# Pair_3.net
KiCad netlist of a schematic drawn in Altium Designer
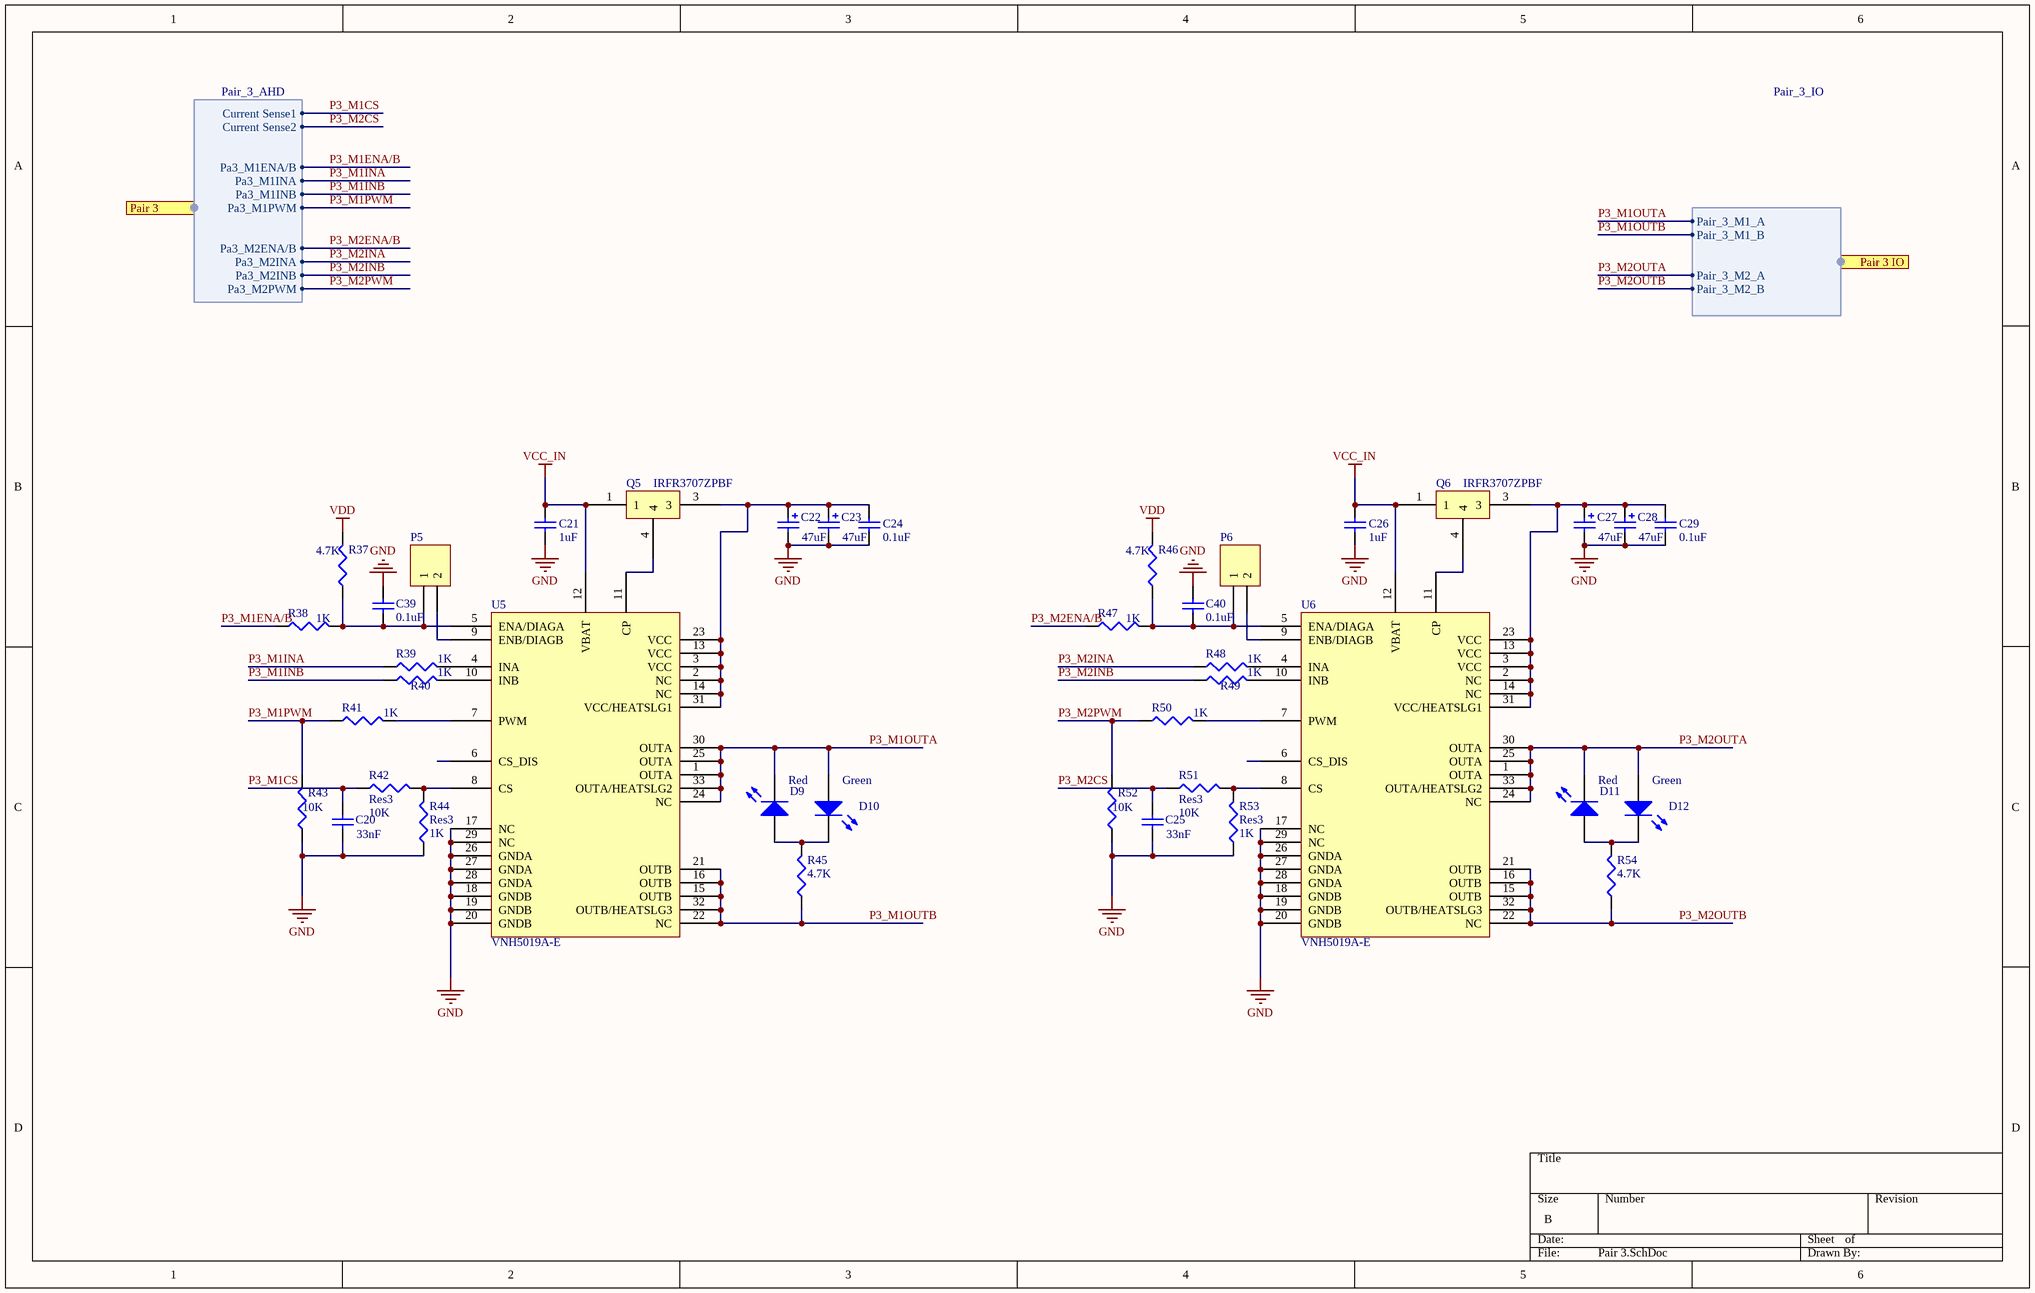
[diagram p0: Pair 3.SchDoc]

(export (version "E")
  (design (tool "Eeschema 10.0.6"))
  (components
    (comp (ref "C20")
      (value "33nF")
      (footprint "1608[0603]")
      (description "Capacitor (Semiconductor SIM Model)")
      (fields (field (name "Comment") "Cap Semi") (field (name "PUBLISHER") "Altium Limited"))
      (libsource (lib "Miscellaneous Devices") (part "Cap Semi"))
    )
    (comp (ref "C21")
      (value "1uF")
      (footprint "1608[0603]")
      (description "Capacitor (Semiconductor SIM Model)")
      (fields (field (name "Comment") "Cap Semi") (field (name "PUBLISHER") "Altium Limited"))
      (libsource (lib "Miscellaneous Devices") (part "Cap Semi"))
    )
    (comp (ref "C22")
      (value "47uF")
      (footprint "CAPPR2-5x6.8")
      (description "Polarized Capacitor (Axial)")
      (fields (field (name "Comment") "Cap Pol2") (field (name "PUBLISHER") "Altium Limited"))
      (libsource (lib "Miscellaneous Devices") (part "Cap Pol2"))
    )
    (comp (ref "C23")
      (value "47uF")
      (footprint "CAPPR2-5x6.8")
      (description "Polarized Capacitor (Axial)")
      (fields (field (name "Comment") "Cap Pol2") (field (name "PUBLISHER") "Altium Limited"))
      (libsource (lib "Miscellaneous Devices") (part "Cap Pol2"))
    )
    (comp (ref "C24")
      (value "0.1uF")
      (footprint "C1206")
      (description "Capacitor (Semiconductor SIM Model)")
      (fields (field (name "Comment") "Cap Semi") (field (name "PUBLISHER") "Altium Limited"))
      (libsource (lib "Miscellaneous Devices") (part "Cap Semi"))
    )
    (comp (ref "C25")
      (value "33nF")
      (footprint "1608[0603]")
      (description "Capacitor (Semiconductor SIM Model)")
      (fields (field (name "Comment") "Cap Semi") (field (name "PUBLISHER") "Altium Limited"))
      (libsource (lib "Miscellaneous Devices") (part "Cap Semi"))
    )
    (comp (ref "C26")
      (value "1uF")
      (footprint "1608[0603]")
      (description "Capacitor (Semiconductor SIM Model)")
      (fields (field (name "Comment") "Cap Semi") (field (name "PUBLISHER") "Altium Limited"))
      (libsource (lib "Miscellaneous Devices") (part "Cap Semi"))
    )
    (comp (ref "C27")
      (value "47uF")
      (footprint "CAPPR2-5x6.8")
      (description "Polarized Capacitor (Axial)")
      (fields (field (name "Comment") "Cap Pol2") (field (name "PUBLISHER") "Altium Limited"))
      (libsource (lib "Miscellaneous Devices") (part "Cap Pol2"))
    )
    (comp (ref "C28")
      (value "47uF")
      (footprint "CAPPR2-5x6.8")
      (description "Polarized Capacitor (Axial)")
      (fields (field (name "Comment") "Cap Pol2") (field (name "PUBLISHER") "Altium Limited"))
      (libsource (lib "Miscellaneous Devices") (part "Cap Pol2"))
    )
    (comp (ref "C29")
      (value "0.1uF")
      (footprint "C1206")
      (description "Capacitor (Semiconductor SIM Model)")
      (fields (field (name "Comment") "Cap Semi") (field (name "PUBLISHER") "Altium Limited"))
      (libsource (lib "Miscellaneous Devices") (part "Cap Semi"))
    )
    (comp (ref "C39")
      (value "0.1uF")
      (footprint "1608[0603]")
      (description "Capacitor (Semiconductor SIM Model)")
      (fields (field (name "Comment") "Cap Semi") (field (name "PUBLISHER") "Altium Limited"))
      (libsource (lib "Miscellaneous Devices") (part "Cap Semi"))
    )
    (comp (ref "C40")
      (value "0.1uF")
      (footprint "1608[0603]")
      (description "Capacitor (Semiconductor SIM Model)")
      (fields (field (name "Comment") "Cap Semi") (field (name "PUBLISHER") "Altium Limited"))
      (libsource (lib "Miscellaneous Devices") (part "Cap Semi"))
    )
    (comp (ref "D9")
      (value "LED2")
      (footprint "3.2X1.6X1.1")
      (description "Typical RED, GREEN, YELLOW, AMBER GaAs LED")
      (fields (field (name "PUBLISHER") "Altium Limited"))
      (libsource (lib "Miscellaneous Devices") (part "LED2"))
    )
    (comp (ref "D10")
      (value "LED2")
      (footprint "3.2X1.6X1.1")
      (description "Typical RED, GREEN, YELLOW, AMBER GaAs LED")
      (fields (field (name "PUBLISHER") "Altium Limited"))
      (libsource (lib "Miscellaneous Devices") (part "LED2"))
    )
    (comp (ref "D11")
      (value "LED2")
      (footprint "3.2X1.6X1.1")
      (description "Typical RED, GREEN, YELLOW, AMBER GaAs LED")
      (fields (field (name "PUBLISHER") "Altium Limited"))
      (libsource (lib "Miscellaneous Devices") (part "LED2"))
    )
    (comp (ref "D12")
      (value "LED2")
      (footprint "3.2X1.6X1.1")
      (description "Typical RED, GREEN, YELLOW, AMBER GaAs LED")
      (fields (field (name "PUBLISHER") "Altium Limited"))
      (libsource (lib "Miscellaneous Devices") (part "LED2"))
    )
    (comp (ref "P5")
      (value "Header 2")
      (footprint "HDR1X2")
      (description "Header, 2-Pin")
      (fields (field (name "PUBLISHER") "Altium Limited"))
      (libsource (lib "Miscellaneous Connectors") (part "Header 2"))
    )
    (comp (ref "P6")
      (value "Header 2")
      (footprint "HDR1X2")
      (description "Header, 2-Pin")
      (fields (field (name "PUBLISHER") "Altium Limited"))
      (libsource (lib "Miscellaneous Connectors") (part "Header 2"))
    )
    (comp (ref "Q5")
      (value "IRFR3707ZPBF")
      (footprint "IRFR3707ZPBF")
      (description "Power FET")
      (libsource (lib "Thruster Shield Part Library") (part "IRFR3707ZPBF"))
    )
    (comp (ref "Q6")
      (value "IRFR3707ZPBF")
      (footprint "IRFR3707ZPBF")
      (description "Power FET")
      (libsource (lib "Thruster Shield Part Library") (part "IRFR3707ZPBF"))
    )
    (comp (ref "R37")
      (value "4.7K")
      (footprint "RESC1608L")
      (description "Resistor")
      (fields (field (name "Comment") "Res3") (field (name "PUBLISHER") "Altium Limited"))
      (libsource (lib "Miscellaneous Devices") (part "Res3"))
    )
    (comp (ref "R38")
      (value "1K")
      (footprint "RESC1608L")
      (description "Resistor")
      (fields (field (name "Comment") "Res3") (field (name "PUBLISHER") "Altium Limited"))
      (libsource (lib "Miscellaneous Devices") (part "Res3"))
    )
    (comp (ref "R39")
      (value "1K")
      (footprint "RESC1608L")
      (description "Resistor")
      (fields (field (name "Comment") "Res3") (field (name "PUBLISHER") "Altium Limited"))
      (libsource (lib "Miscellaneous Devices") (part "Res3"))
    )
    (comp (ref "R40")
      (value "1K")
      (footprint "RESC1608L")
      (description "Resistor")
      (fields (field (name "Comment") "Res3") (field (name "PUBLISHER") "Altium Limited"))
      (libsource (lib "Miscellaneous Devices") (part "Res3"))
    )
    (comp (ref "R41")
      (value "1K")
      (footprint "RESC1608L")
      (description "Resistor")
      (fields (field (name "Comment") "Res3") (field (name "PUBLISHER") "Altium Limited"))
      (libsource (lib "Miscellaneous Devices") (part "Res3"))
    )
    (comp (ref "R42")
      (value "Res3")
      (footprint "RESC1608L")
      (description "Resistor")
      (fields (field (name "ALTIUM_VALUE") "10K") (field (name "PUBLISHER") "Altium Limited"))
      (libsource (lib "Miscellaneous Devices") (part "Res3"))
    )
    (comp (ref "R43")
      (value "10K")
      (footprint "RESC1608L")
      (description "Resistor")
      (fields (field (name "Comment") "Res3") (field (name "PUBLISHER") "Altium Limited"))
      (libsource (lib "Miscellaneous Devices") (part "Res3"))
    )
    (comp (ref "R44")
      (value "Res3")
      (footprint "RESC1608L")
      (description "Resistor")
      (fields (field (name "ALTIUM_VALUE") "1K") (field (name "PUBLISHER") "Altium Limited"))
      (libsource (lib "Miscellaneous Devices") (part "Res3"))
    )
    (comp (ref "R45")
      (value "4.7K")
      (footprint "0805 SMD Resistor")
      (description "Resistor")
      (fields (field (name "Comment") "Res3") (field (name "PUBLISHER") "Altium Limited"))
      (libsource (lib "Miscellaneous Devices") (part "Res3"))
    )
    (comp (ref "R46")
      (value "4.7K")
      (footprint "RESC1608L")
      (description "Resistor")
      (fields (field (name "Comment") "Res3") (field (name "PUBLISHER") "Altium Limited"))
      (libsource (lib "Miscellaneous Devices") (part "Res3"))
    )
    (comp (ref "R47")
      (value "1K")
      (footprint "RESC1608L")
      (description "Resistor")
      (fields (field (name "Comment") "Res3") (field (name "PUBLISHER") "Altium Limited"))
      (libsource (lib "Miscellaneous Devices") (part "Res3"))
    )
    (comp (ref "R48")
      (value "1K")
      (footprint "RESC1608L")
      (description "Resistor")
      (fields (field (name "Comment") "Res3") (field (name "PUBLISHER") "Altium Limited"))
      (libsource (lib "Miscellaneous Devices") (part "Res3"))
    )
    (comp (ref "R49")
      (value "1K")
      (footprint "RESC1608L")
      (description "Resistor")
      (fields (field (name "Comment") "Res3") (field (name "PUBLISHER") "Altium Limited"))
      (libsource (lib "Miscellaneous Devices") (part "Res3"))
    )
    (comp (ref "R50")
      (value "1K")
      (footprint "RESC1608L")
      (description "Resistor")
      (fields (field (name "Comment") "Res3") (field (name "PUBLISHER") "Altium Limited"))
      (libsource (lib "Miscellaneous Devices") (part "Res3"))
    )
    (comp (ref "R51")
      (value "Res3")
      (footprint "RESC1608L")
      (description "Resistor")
      (fields (field (name "ALTIUM_VALUE") "10K") (field (name "PUBLISHER") "Altium Limited"))
      (libsource (lib "Miscellaneous Devices") (part "Res3"))
    )
    (comp (ref "R52")
      (value "10K")
      (footprint "RESC1608L")
      (description "Resistor")
      (fields (field (name "Comment") "Res3") (field (name "PUBLISHER") "Altium Limited"))
      (libsource (lib "Miscellaneous Devices") (part "Res3"))
    )
    (comp (ref "R53")
      (value "Res3")
      (footprint "RESC1608L")
      (description "Resistor")
      (fields (field (name "ALTIUM_VALUE") "1K") (field (name "PUBLISHER") "Altium Limited"))
      (libsource (lib "Miscellaneous Devices") (part "Res3"))
    )
    (comp (ref "R54")
      (value "4.7K")
      (footprint "0805 SMD Resistor")
      (description "Resistor")
      (fields (field (name "Comment") "Res3") (field (name "PUBLISHER") "Altium Limited"))
      (libsource (lib "Miscellaneous Devices") (part "Res3"))
    )
    (comp (ref "U5")
      (value "VNH5019A-E")
      (footprint "VNH5019A-E")
      (description "VNH5019A-E H-Bridge")
      (libsource (lib "Thruster Shield Part Library") (part "VNH5019A-E"))
    )
    (comp (ref "U6")
      (value "VNH5019A-E")
      (footprint "VNH5019A-E")
      (description "VNH5019A-E H-Bridge")
      (libsource (lib "Thruster Shield Part Library") (part "VNH5019A-E"))
    )
  )
  (nets
    (net (code "3") (name "/P3_M1CS") (class "Default")
      (node (ref "C20") (pin "2") (pinfunction "2_2") (pintype "passive"))
      (node (ref "R42") (pin "1") (pinfunction "1_1") (pintype "passive"))
    )
    (net (code "4") (name "/P3_M1ENA{slash}B") (class "Default")
      (node (ref "R38") (pin "1") (pinfunction "1_1") (pintype "passive"))
    )
    (net (code "5") (name "/P3_M1INA") (class "Default")
      (node (ref "R39") (pin "1") (pinfunction "1_1") (pintype "passive"))
    )
    (net (code "6") (name "/P3_M1INB") (class "Default")
      (node (ref "R40") (pin "1") (pinfunction "1_1") (pintype "passive"))
    )
    (net (code "7") (name "/P3_M1OUTA") (class "Default")
      (node (ref "D10") (pin "1") (pinfunction "A_1") (pintype "passive"))
      (node (ref "D9") (pin "2") (pinfunction "K_2") (pintype "passive"))
      (node (ref "U5") (pin "1") (pinfunction "OUTA_1") (pintype "passive"))
      (node (ref "U5") (pin "24") (pinfunction "NC_24") (pintype "passive"))
      (node (ref "U5") (pin "25") (pinfunction "OUTA_25") (pintype "passive"))
      (node (ref "U5") (pin "30") (pinfunction "OUTA_30") (pintype "passive"))
      (node (ref "U5") (pin "33") (pinfunction "OUTA/HEATSLG2_33") (pintype "passive"))
    )
    (net (code "8") (name "/P3_M1OUTB") (class "Default")
      (node (ref "R45") (pin "1") (pinfunction "1_1") (pintype "passive"))
      (node (ref "U5") (pin "15") (pinfunction "OUTB_15") (pintype "passive"))
      (node (ref "U5") (pin "16") (pinfunction "OUTB_16") (pintype "passive"))
      (node (ref "U5") (pin "21") (pinfunction "OUTB_21") (pintype "passive"))
      (node (ref "U5") (pin "22") (pinfunction "NC_22") (pintype "passive"))
      (node (ref "U5") (pin "32") (pinfunction "OUTB/HEATSLG3_32") (pintype "passive"))
    )
    (net (code "9") (name "/P3_M1PWM") (class "Default")
      (node (ref "R41") (pin "1") (pinfunction "1_1") (pintype "passive"))
      (node (ref "R43") (pin "2") (pinfunction "2_2") (pintype "passive"))
    )
    (net (code "10") (name "/P3_M2CS") (class "Default")
      (node (ref "C25") (pin "2") (pinfunction "2_2") (pintype "passive"))
      (node (ref "R51") (pin "1") (pinfunction "1_1") (pintype "passive"))
    )
    (net (code "11") (name "/P3_M2ENA{slash}B") (class "Default")
      (node (ref "R47") (pin "1") (pinfunction "1_1") (pintype "passive"))
    )
    (net (code "12") (name "/P3_M2INA") (class "Default")
      (node (ref "R48") (pin "1") (pinfunction "1_1") (pintype "passive"))
    )
    (net (code "13") (name "/P3_M2INB") (class "Default")
      (node (ref "R49") (pin "1") (pinfunction "1_1") (pintype "passive"))
    )
    (net (code "14") (name "/P3_M2OUTA") (class "Default")
      (node (ref "D11") (pin "2") (pinfunction "K_2") (pintype "passive"))
      (node (ref "D12") (pin "1") (pinfunction "A_1") (pintype "passive"))
      (node (ref "U6") (pin "1") (pinfunction "OUTA_1") (pintype "passive"))
      (node (ref "U6") (pin "24") (pinfunction "NC_24") (pintype "passive"))
      (node (ref "U6") (pin "25") (pinfunction "OUTA_25") (pintype "passive"))
      (node (ref "U6") (pin "30") (pinfunction "OUTA_30") (pintype "passive"))
      (node (ref "U6") (pin "33") (pinfunction "OUTA/HEATSLG2_33") (pintype "passive"))
    )
    (net (code "15") (name "/P3_M2OUTB") (class "Default")
      (node (ref "R54") (pin "1") (pinfunction "1_1") (pintype "passive"))
      (node (ref "U6") (pin "15") (pinfunction "OUTB_15") (pintype "passive"))
      (node (ref "U6") (pin "16") (pinfunction "OUTB_16") (pintype "passive"))
      (node (ref "U6") (pin "21") (pinfunction "OUTB_21") (pintype "passive"))
      (node (ref "U6") (pin "22") (pinfunction "NC_22") (pintype "passive"))
      (node (ref "U6") (pin "32") (pinfunction "OUTB/HEATSLG3_32") (pintype "passive"))
    )
    (net (code "16") (name "/P3_M2PWM") (class "Default")
      (node (ref "R50") (pin "1") (pinfunction "1_1") (pintype "passive"))
      (node (ref "R52") (pin "2") (pinfunction "2_2") (pintype "passive"))
    )
    (net (code "19") (name "GND") (class "Default")
      (node (ref "C20") (pin "1") (pinfunction "1_1") (pintype "passive"))
      (node (ref "C21") (pin "1") (pinfunction "1_1") (pintype "passive"))
      (node (ref "C22") (pin "2") (pinfunction "2_2") (pintype "passive"))
      (node (ref "C23") (pin "2") (pinfunction "2_2") (pintype "passive"))
      (node (ref "C24") (pin "1") (pinfunction "1_1") (pintype "passive"))
      (node (ref "C25") (pin "1") (pinfunction "1_1") (pintype "passive"))
      (node (ref "C26") (pin "1") (pinfunction "1_1") (pintype "passive"))
      (node (ref "C27") (pin "2") (pinfunction "2_2") (pintype "passive"))
      (node (ref "C28") (pin "2") (pinfunction "2_2") (pintype "passive"))
      (node (ref "C29") (pin "1") (pinfunction "1_1") (pintype "passive"))
      (node (ref "C39") (pin "1") (pinfunction "1_1") (pintype "passive"))
      (node (ref "C40") (pin "1") (pinfunction "1_1") (pintype "passive"))
      (node (ref "R43") (pin "1") (pinfunction "1_1") (pintype "passive"))
      (node (ref "R44") (pin "1") (pinfunction "1_1") (pintype "passive"))
      (node (ref "R52") (pin "1") (pinfunction "1_1") (pintype "passive"))
      (node (ref "R53") (pin "1") (pinfunction "1_1") (pintype "passive"))
      (node (ref "U5") (pin "17") (pinfunction "NC_17") (pintype "passive"))
      (node (ref "U5") (pin "18") (pinfunction "GNDB_18") (pintype "passive"))
      (node (ref "U5") (pin "19") (pinfunction "GNDB_19") (pintype "passive"))
      (node (ref "U5") (pin "20") (pinfunction "GNDB_20") (pintype "passive"))
      (node (ref "U5") (pin "26") (pinfunction "GNDA_26") (pintype "passive"))
      (node (ref "U5") (pin "27") (pinfunction "GNDA_27") (pintype "passive"))
      (node (ref "U5") (pin "28") (pinfunction "GNDA_28") (pintype "passive"))
      (node (ref "U5") (pin "29") (pinfunction "NC_29") (pintype "passive"))
      (node (ref "U6") (pin "17") (pinfunction "NC_17") (pintype "passive"))
      (node (ref "U6") (pin "18") (pinfunction "GNDB_18") (pintype "passive"))
      (node (ref "U6") (pin "19") (pinfunction "GNDB_19") (pintype "passive"))
      (node (ref "U6") (pin "20") (pinfunction "GNDB_20") (pintype "passive"))
      (node (ref "U6") (pin "26") (pinfunction "GNDA_26") (pintype "passive"))
      (node (ref "U6") (pin "27") (pinfunction "GNDA_27") (pintype "passive"))
      (node (ref "U6") (pin "28") (pinfunction "GNDA_28") (pintype "passive"))
      (node (ref "U6") (pin "29") (pinfunction "NC_29") (pintype "passive"))
    )
    (net (code "20") (name "Net-(D10-K)") (class "Default")
      (node (ref "D10") (pin "2") (pinfunction "K_2") (pintype "passive"))
      (node (ref "D9") (pin "1") (pinfunction "A_1") (pintype "passive"))
      (node (ref "R45") (pin "2") (pinfunction "2_2") (pintype "passive"))
    )
    (net (code "21") (name "Net-(D11-A)") (class "Default")
      (node (ref "D11") (pin "1") (pinfunction "A_1") (pintype "passive"))
      (node (ref "D12") (pin "2") (pinfunction "K_2") (pintype "passive"))
      (node (ref "R54") (pin "2") (pinfunction "2_2") (pintype "passive"))
    )
    (net (code "22") (name "Net-(U5-CP)") (class "Default")
      (node (ref "Q5") (pin "4") (pinfunction "4_4") (pintype "passive"))
      (node (ref "U5") (pin "11") (pinfunction "CP_11") (pintype "passive"))
    )
    (net (code "23") (name "Net-(U5-CS)") (class "Default")
      (node (ref "R42") (pin "2") (pinfunction "2_2") (pintype "passive"))
      (node (ref "R44") (pin "2") (pinfunction "2_2") (pintype "passive"))
      (node (ref "U5") (pin "8") (pinfunction "CS_8") (pintype "passive"))
    )
    (net (code "24") (name "Net-(U5-ENA{slash}DIAGA)") (class "Default")
      (node (ref "C39") (pin "2") (pinfunction "2_2") (pintype "passive"))
      (node (ref "P5") (pin "1") (pinfunction "1_1") (pintype "passive"))
      (node (ref "R37") (pin "1") (pinfunction "1_1") (pintype "passive"))
      (node (ref "R38") (pin "2") (pinfunction "2_2") (pintype "passive"))
      (node (ref "U5") (pin "5") (pinfunction "ENA/DIAGA_5") (pintype "passive"))
    )
    (net (code "25") (name "Net-(U5-ENB{slash}DIAGB)") (class "Default")
      (node (ref "P5") (pin "2") (pinfunction "2_2") (pintype "passive"))
      (node (ref "U5") (pin "9") (pinfunction "ENB/DIAGB_9") (pintype "passive"))
    )
    (net (code "26") (name "Net-(U5-INA)") (class "Default")
      (node (ref "R39") (pin "2") (pinfunction "2_2") (pintype "passive"))
      (node (ref "U5") (pin "4") (pinfunction "INA_4") (pintype "passive"))
    )
    (net (code "27") (name "Net-(U5-INB)") (class "Default")
      (node (ref "R40") (pin "2") (pinfunction "2_2") (pintype "passive"))
      (node (ref "U5") (pin "10") (pinfunction "INB_10") (pintype "passive"))
    )
    (net (code "28") (name "Net-(U5-PWM)") (class "Default")
      (node (ref "R41") (pin "2") (pinfunction "2_2") (pintype "passive"))
      (node (ref "U5") (pin "7") (pinfunction "PWM_7") (pintype "passive"))
    )
    (net (code "29") (name "Net-(U5-VCC{slash}HEATSLG1)") (class "Default")
      (node (ref "C22") (pin "1") (pinfunction "1_1") (pintype "passive"))
      (node (ref "C23") (pin "1") (pinfunction "1_1") (pintype "passive"))
      (node (ref "C24") (pin "2") (pinfunction "2_2") (pintype "passive"))
      (node (ref "Q5") (pin "3") (pinfunction "3_3") (pintype "passive"))
      (node (ref "U5") (pin "13") (pinfunction "VCC_13") (pintype "passive"))
      (node (ref "U5") (pin "14") (pinfunction "NC_14") (pintype "passive"))
      (node (ref "U5") (pin "2") (pinfunction "NC_2") (pintype "passive"))
      (node (ref "U5") (pin "23") (pinfunction "VCC_23") (pintype "passive"))
      (node (ref "U5") (pin "3") (pinfunction "VCC_3") (pintype "passive"))
      (node (ref "U5") (pin "31") (pinfunction "VCC/HEATSLG1_31") (pintype "passive"))
    )
    (net (code "30") (name "Net-(U6-CP)") (class "Default")
      (node (ref "Q6") (pin "4") (pinfunction "4_4") (pintype "passive"))
      (node (ref "U6") (pin "11") (pinfunction "CP_11") (pintype "passive"))
    )
    (net (code "31") (name "Net-(U6-CS)") (class "Default")
      (node (ref "R51") (pin "2") (pinfunction "2_2") (pintype "passive"))
      (node (ref "R53") (pin "2") (pinfunction "2_2") (pintype "passive"))
      (node (ref "U6") (pin "8") (pinfunction "CS_8") (pintype "passive"))
    )
    (net (code "32") (name "Net-(U6-ENA{slash}DIAGA)") (class "Default")
      (node (ref "C40") (pin "2") (pinfunction "2_2") (pintype "passive"))
      (node (ref "P6") (pin "1") (pinfunction "1_1") (pintype "passive"))
      (node (ref "R46") (pin "1") (pinfunction "1_1") (pintype "passive"))
      (node (ref "R47") (pin "2") (pinfunction "2_2") (pintype "passive"))
      (node (ref "U6") (pin "5") (pinfunction "ENA/DIAGA_5") (pintype "passive"))
    )
    (net (code "33") (name "Net-(U6-ENB{slash}DIAGB)") (class "Default")
      (node (ref "P6") (pin "2") (pinfunction "2_2") (pintype "passive"))
      (node (ref "U6") (pin "9") (pinfunction "ENB/DIAGB_9") (pintype "passive"))
    )
    (net (code "34") (name "Net-(U6-INA)") (class "Default")
      (node (ref "R48") (pin "2") (pinfunction "2_2") (pintype "passive"))
      (node (ref "U6") (pin "4") (pinfunction "INA_4") (pintype "passive"))
    )
    (net (code "35") (name "Net-(U6-INB)") (class "Default")
      (node (ref "R49") (pin "2") (pinfunction "2_2") (pintype "passive"))
      (node (ref "U6") (pin "10") (pinfunction "INB_10") (pintype "passive"))
    )
    (net (code "36") (name "Net-(U6-PWM)") (class "Default")
      (node (ref "R50") (pin "2") (pinfunction "2_2") (pintype "passive"))
      (node (ref "U6") (pin "7") (pinfunction "PWM_7") (pintype "passive"))
    )
    (net (code "37") (name "Net-(U6-VCC{slash}HEATSLG1)") (class "Default")
      (node (ref "C27") (pin "1") (pinfunction "1_1") (pintype "passive"))
      (node (ref "C28") (pin "1") (pinfunction "1_1") (pintype "passive"))
      (node (ref "C29") (pin "2") (pinfunction "2_2") (pintype "passive"))
      (node (ref "Q6") (pin "3") (pinfunction "3_3") (pintype "passive"))
      (node (ref "U6") (pin "13") (pinfunction "VCC_13") (pintype "passive"))
      (node (ref "U6") (pin "14") (pinfunction "NC_14") (pintype "passive"))
      (node (ref "U6") (pin "2") (pinfunction "NC_2") (pintype "passive"))
      (node (ref "U6") (pin "23") (pinfunction "VCC_23") (pintype "passive"))
      (node (ref "U6") (pin "3") (pinfunction "VCC_3") (pintype "passive"))
      (node (ref "U6") (pin "31") (pinfunction "VCC/HEATSLG1_31") (pintype "passive"))
    )
    (net (code "38") (name "VCC_IN") (class "Default")
      (node (ref "C21") (pin "2") (pinfunction "2_2") (pintype "passive"))
      (node (ref "C26") (pin "2") (pinfunction "2_2") (pintype "passive"))
      (node (ref "Q5") (pin "1") (pinfunction "1_1") (pintype "passive"))
      (node (ref "Q6") (pin "1") (pinfunction "1_1") (pintype "passive"))
      (node (ref "U5") (pin "12") (pinfunction "VBAT_12") (pintype "passive"))
      (node (ref "U6") (pin "12") (pinfunction "VBAT_12") (pintype "passive"))
    )
    (net (code "39") (name "VDD") (class "Default")
      (node (ref "R37") (pin "2") (pinfunction "2_2") (pintype "passive"))
      (node (ref "R46") (pin "2") (pinfunction "2_2") (pintype "passive"))
    )
    (net (code "40") (name "unconnected-(U5-CS_DIS-Pad6)") (class "Default")
      (node (ref "U5") (pin "6") (pinfunction "CS_DIS_6") (pintype "passive"))
    )
    (net (code "41") (name "unconnected-(U6-CS_DIS-Pad6)") (class "Default")
      (node (ref "U6") (pin "6") (pinfunction "CS_DIS_6") (pintype "passive"))
    )
  )
)
